# Top_Level.net
KiCad netlist of a schematic drawn in Altium Designer
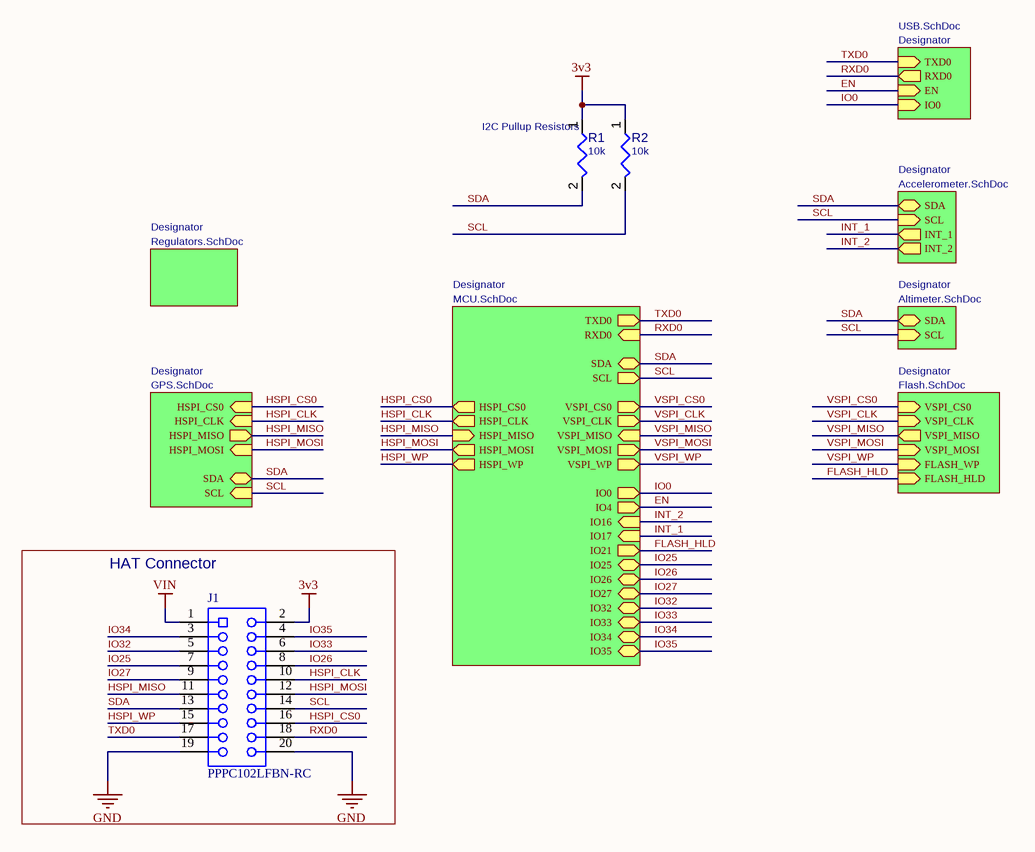
[diagram p0: Top Level.SchDoc]

(export (version "E")
  (design (tool "Eeschema 10.0.6"))
  (components
    (comp (ref "J1")
      (value "PPPC102LFBN-RC")
      (footprint "SLIN-PPPC102LFBN-RC_V")
      (fields (field (name "MANUFACTURER") "Sullins"))
      (libsource (lib "RIT Launch Initiative") (part "CN-2P-F-R20"))
    )
    (comp (ref "R1")
      (value "10k")
      (footprint "RESC0402(1005)_L")
      (description "Chip Resistor, 10 kOhms, +/-1 %, 63 mW, -55 to 125 degC, 0402")
      (fields (field (name "POWER") "63mW") (field (name "TOLERANCE") "1%"))
      (libsource (lib "RIT Launch Initiative") (part "RES-2"))
    )
    (comp (ref "R2")
      (value "10k")
      (footprint "RESC0402(1005)_L")
      (description "Chip Resistor, 10 kOhms, +/-1 %, 63 mW, -55 to 125 degC, 0402")
      (fields (field (name "POWER") "63mW") (field (name "TOLERANCE") "1%"))
      (libsource (lib "RIT Launch Initiative") (part "RES-2"))
    )
  )
  (nets
    (net (code "3") (name "/HSPI_CLK") (class "Default")
      (node (ref "J1") (pin "10") (pinfunction "10_10") (pintype "passive"))
    )
    (net (code "4") (name "/HSPI_CS0") (class "Default")
      (node (ref "J1") (pin "16") (pinfunction "16_16") (pintype "passive"))
    )
    (net (code "5") (name "/HSPI_MISO") (class "Default")
      (node (ref "J1") (pin "11") (pinfunction "11_11") (pintype "passive"))
    )
    (net (code "6") (name "/HSPI_MOSI") (class "Default")
      (node (ref "J1") (pin "12") (pinfunction "12_12") (pintype "passive"))
    )
    (net (code "7") (name "/HSPI_WP") (class "Default")
      (node (ref "J1") (pin "15") (pinfunction "15_15") (pintype "passive"))
    )
    (net (code "11") (name "/IO25") (class "Default")
      (node (ref "J1") (pin "7") (pinfunction "7_7") (pintype "passive"))
    )
    (net (code "12") (name "/IO26") (class "Default")
      (node (ref "J1") (pin "8") (pinfunction "8_8") (pintype "passive"))
    )
    (net (code "13") (name "/IO27") (class "Default")
      (node (ref "J1") (pin "9") (pinfunction "9_9") (pintype "passive"))
    )
    (net (code "14") (name "/IO32") (class "Default")
      (node (ref "J1") (pin "5") (pinfunction "5_5") (pintype "passive"))
    )
    (net (code "15") (name "/IO33") (class "Default")
      (node (ref "J1") (pin "6") (pinfunction "6_6") (pintype "passive"))
    )
    (net (code "16") (name "/IO34") (class "Default")
      (node (ref "J1") (pin "3") (pinfunction "3_3") (pintype "passive"))
    )
    (net (code "17") (name "/IO35") (class "Default")
      (node (ref "J1") (pin "4") (pinfunction "4_4") (pintype "passive"))
    )
    (net (code "18") (name "/RXD0") (class "Default")
      (node (ref "J1") (pin "18") (pinfunction "18_18") (pintype "passive"))
    )
    (net (code "19") (name "/SCL") (class "Default")
      (node (ref "J1") (pin "14") (pinfunction "14_14") (pintype "passive"))
      (node (ref "R2") (pin "2") (pinfunction "2_2") (pintype "passive"))
    )
    (net (code "20") (name "/SDA") (class "Default")
      (node (ref "J1") (pin "13") (pinfunction "13_13") (pintype "passive"))
      (node (ref "R1") (pin "2") (pinfunction "2_2") (pintype "passive"))
    )
    (net (code "21") (name "/TXD0") (class "Default")
      (node (ref "J1") (pin "17") (pinfunction "17_17") (pintype "passive"))
    )
    (net (code "27") (name "3v3") (class "Default")
      (node (ref "J1") (pin "2") (pinfunction "2_2") (pintype "passive"))
      (node (ref "R1") (pin "1") (pinfunction "1_1") (pintype "passive"))
      (node (ref "R2") (pin "1") (pinfunction "1_1") (pintype "passive"))
    )
    (net (code "28") (name "GND") (class "Default")
      (node (ref "J1") (pin "19") (pinfunction "19_19") (pintype "passive"))
      (node (ref "J1") (pin "20") (pinfunction "20_20") (pintype "passive"))
    )
    (net (code "29") (name "VIN") (class "Default")
      (node (ref "J1") (pin "1") (pinfunction "1_1") (pintype "passive"))
    )
  )
)
